# capstone_v1_1.net
KiCad netlist of a schematic drawn in Altium Designer
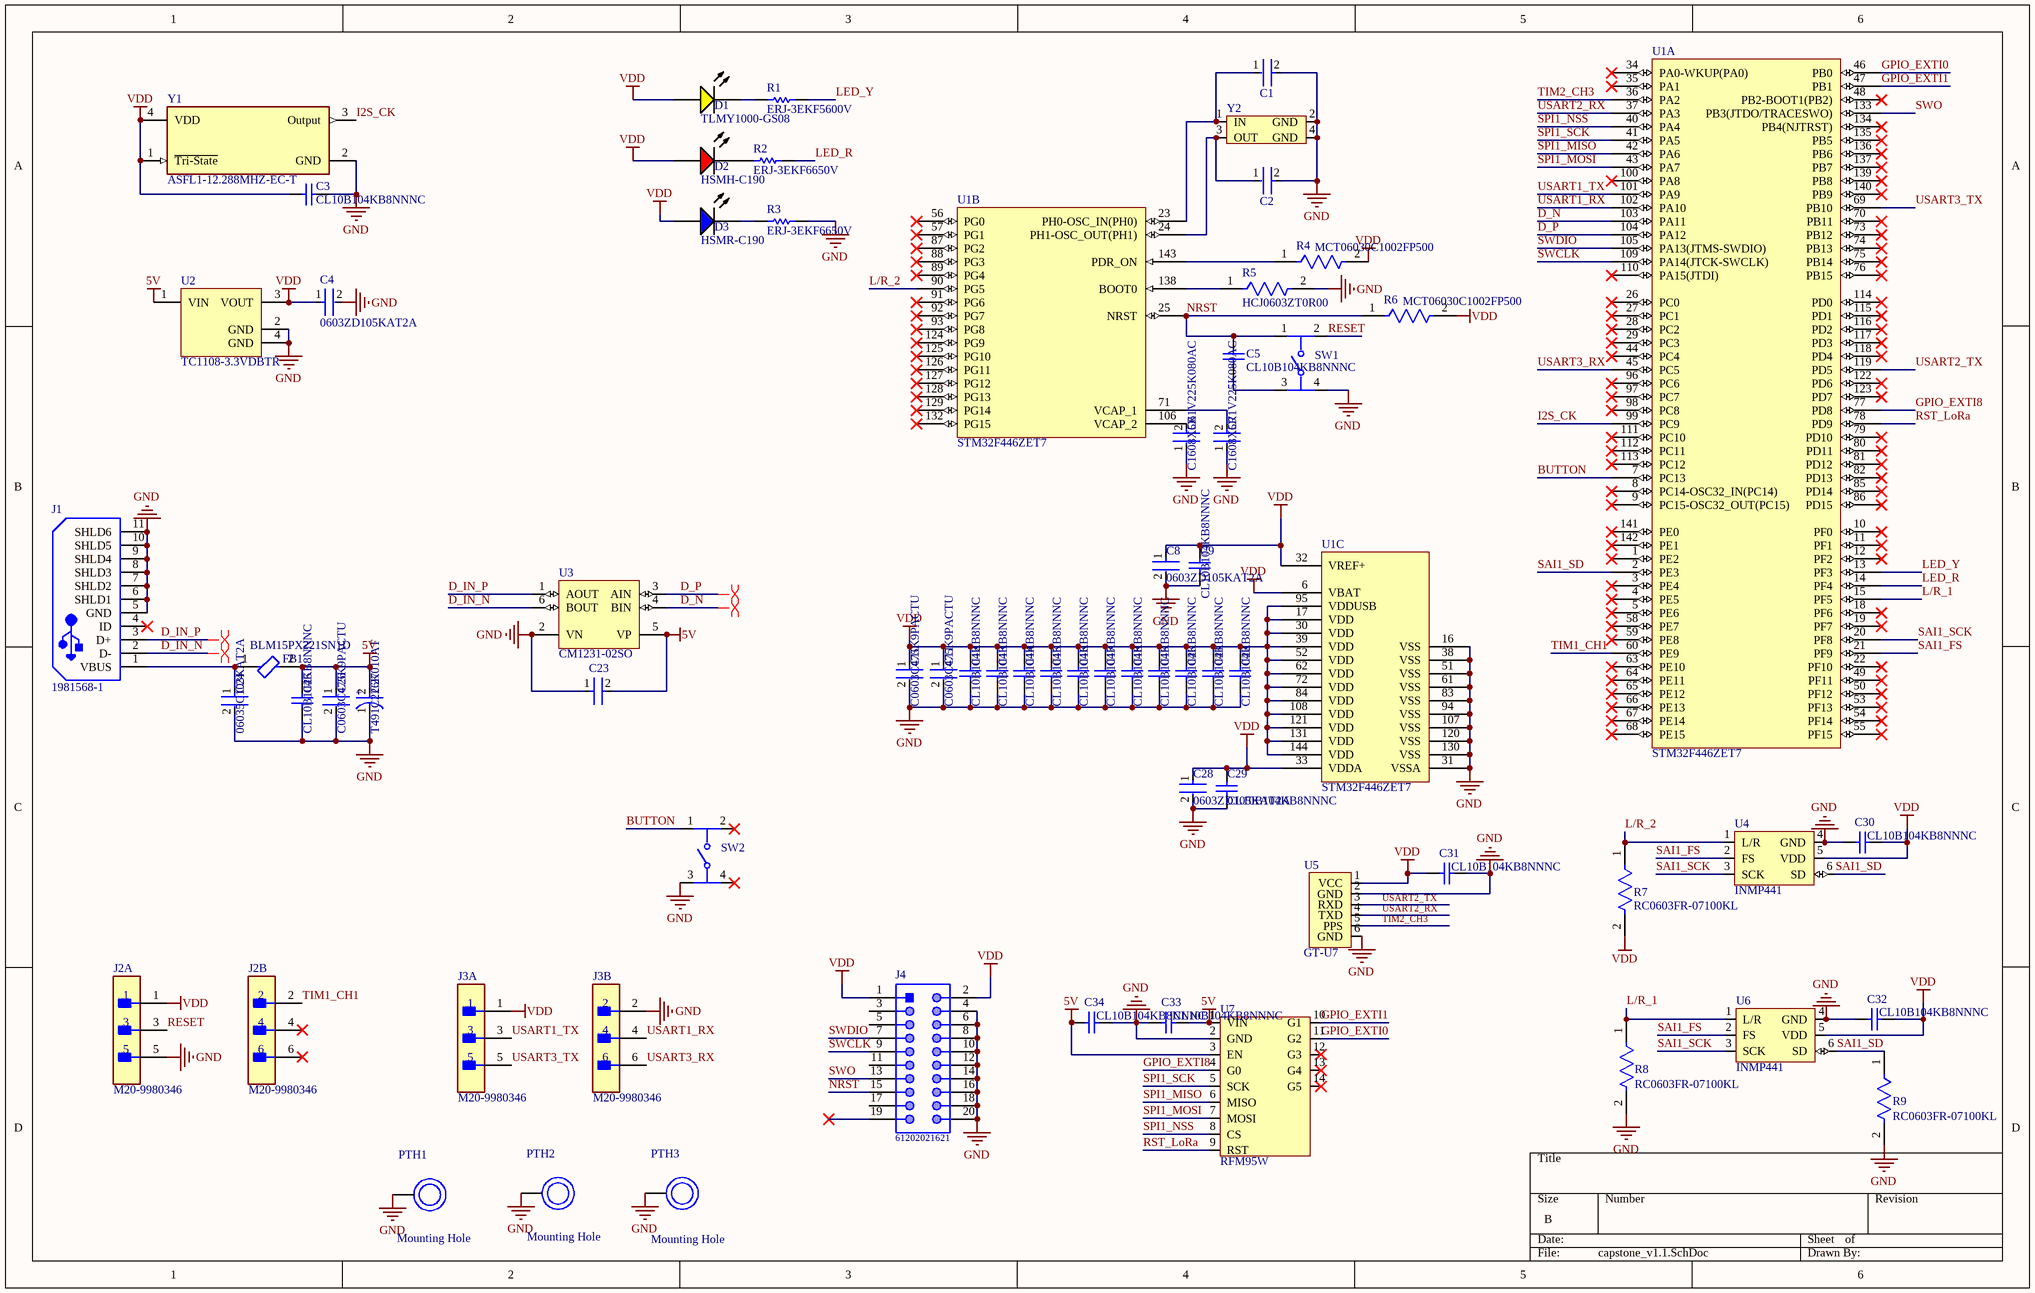
[diagram p0: capstone_v1.1.SchDoc]

(export (version "E")
  (design (tool "Eeschema 10.0.6"))
  (components
    (comp (ref "C1")
      (value "C1608C0G1H150J080AA")
      (footprint "FP-C1608-080-0_1-MFG")
      (description "Multilayer Ceramic Capacitors 15pF ±5% 50V C0G SMD 0603")
      (fields (field (name "VOLTAGE") "50V") (field (name "TOLERANCE") "5%"))
      (libsource (lib "Altium Content Vault") (part "236180d848d6139a670b325ea6854c9"))
    )
    (comp (ref "C2")
      (value "C1608C0G1H150J080AA")
      (footprint "FP-C1608-080-0_1-MFG")
      (description "Multilayer Ceramic Capacitors 15pF ±5% 50V C0G SMD 0603")
      (fields (field (name "VOLTAGE") "50V") (field (name "TOLERANCE") "5%"))
      (libsource (lib "Altium Content Vault") (part "236180d848d6139a670b325ea6854c9"))
    )
    (comp (ref "C3")
      (value "CL10B104KB8NNNC")
      (footprint "SAMS-C0603-2_M")
      (description "Multi-layer Ceramic Capacitor, -55 to 125 degC, 2-Pin SMD (0603), RoHS, Tape and Reel")
      (fields (field (name "MANUFACTURER") "Samsung Electro-Mechanics"))
      (libsource (lib "Altium Content Vault") (part "CAP-NP-2"))
    )
    (comp (ref "C4")
      (value "0603ZD105KAT2A")
      (footprint "FP-0603-L_1_6_0_15-W_0_81-IPC_A")
      (description "General Purpose Ceramic Capacitor, 0603, 1uF, 10%, X5R, 15%, 10V")
      (fields (field (name "TOLERANCE") "10%") (field (name "VOLTAGE") "10V"))
      (libsource (lib "Altium Content Vault") (part "02cd4be3c70576c341d710602a673aa"))
    )
    (comp (ref "C5")
      (value "CL10B104KB8NNNC")
      (footprint "SAMS-C0603-2_M")
      (description "Multi-layer Ceramic Capacitor, -55 to 125 degC, 2-Pin SMD (0603), RoHS, Tape and Reel")
      (fields (field (name "MANUFACTURER") "Samsung Electro-Mechanics"))
      (libsource (lib "Altium Content Vault") (part "CAP-NP-2"))
    )
    (comp (ref "C6")
      (value "C1608X5R1V225K080AC")
      (footprint "FP-C1608-080-0_1-MFG")
      (description "Multilayer Ceramic Capacitors 2.2μF ±10% 35V X5R SMD 0603")
      (fields (field (name "TOLERANCE") "10%") (field (name "VOLTAGE") "35V"))
      (libsource (lib "Altium Content Vault") (part "236180d848d6139a670b325ea6854c9"))
    )
    (comp (ref "C7")
      (value "C1608X5R1V225K080AC")
      (footprint "FP-C1608-080-0_1-MFG")
      (description "Multilayer Ceramic Capacitors 2.2μF ±10% 35V X5R SMD 0603")
      (fields (field (name "TOLERANCE") "10%") (field (name "VOLTAGE") "35V"))
      (libsource (lib "Altium Content Vault") (part "236180d848d6139a670b325ea6854c9"))
    )
    (comp (ref "C8")
      (value "0603ZD105KAT2A")
      (footprint "FP-0603-L_1_6_0_15-W_0_81-IPC_A")
      (description "General Purpose Ceramic Capacitor, 0603, 1uF, 10%, X5R, 15%, 10V")
      (fields (field (name "TOLERANCE") "10%") (field (name "VOLTAGE") "10V"))
      (libsource (lib "Altium Content Vault") (part "02cd4be3c70576c341d710602a673aa"))
    )
    (comp (ref "C9")
      (value "CL10B104KB8NNNC")
      (footprint "SAMS-C0603-2_M")
      (description "Multi-layer Ceramic Capacitor, -55 to 125 degC, 2-Pin SMD (0603), RoHS, Tape and Reel")
      (fields (field (name "MANUFACTURER") "Samsung Electro-Mechanics"))
      (libsource (lib "Altium Content Vault") (part "CAP-NP-2"))
    )
    (comp (ref "C10")
      (value "C0603C475K9PACTU")
      (footprint "FP-C0603-CG-MFG")
      (description "CAP CER 4.7UF 6.3V X5R 0603")
      (fields (field (name "TOLERANCE") "10%") (field (name "MANUFACTURER") "Kemet"))
      (libsource (lib "Altium Content Vault") (part "11868f565c42a9108669ba33697ecf6"))
    )
    (comp (ref "C11")
      (value "C0603C475K9PACTU")
      (footprint "FP-C0603-CG-MFG")
      (description "CAP CER 4.7UF 6.3V X5R 0603")
      (fields (field (name "TOLERANCE") "10%") (field (name "MANUFACTURER") "Kemet"))
      (libsource (lib "Altium Content Vault") (part "11868f565c42a9108669ba33697ecf6"))
    )
    (comp (ref "C12")
      (value "CL10B104KB8NNNC")
      (footprint "SAMS-C0603-2_M")
      (description "Multi-layer Ceramic Capacitor, -55 to 125 degC, 2-Pin SMD (0603), RoHS, Tape and Reel")
      (fields (field (name "MANUFACTURER") "Samsung Electro-Mechanics"))
      (libsource (lib "Altium Content Vault") (part "CAP-NP-2"))
    )
    (comp (ref "C13")
      (value "CL10B104KB8NNNC")
      (footprint "SAMS-C0603-2_M")
      (description "Multi-layer Ceramic Capacitor, -55 to 125 degC, 2-Pin SMD (0603), RoHS, Tape and Reel")
      (fields (field (name "MANUFACTURER") "Samsung Electro-Mechanics"))
      (libsource (lib "Altium Content Vault") (part "CAP-NP-2"))
    )
    (comp (ref "C14")
      (value "CL10B104KB8NNNC")
      (footprint "SAMS-C0603-2_M")
      (description "Multi-layer Ceramic Capacitor, -55 to 125 degC, 2-Pin SMD (0603), RoHS, Tape and Reel")
      (fields (field (name "MANUFACTURER") "Samsung Electro-Mechanics"))
      (libsource (lib "Altium Content Vault") (part "CAP-NP-2"))
    )
    (comp (ref "C15")
      (value "CL10B104KB8NNNC")
      (footprint "SAMS-C0603-2_M")
      (description "Multi-layer Ceramic Capacitor, -55 to 125 degC, 2-Pin SMD (0603), RoHS, Tape and Reel")
      (fields (field (name "MANUFACTURER") "Samsung Electro-Mechanics"))
      (libsource (lib "Altium Content Vault") (part "CAP-NP-2"))
    )
    (comp (ref "C16")
      (value "CL10B104KB8NNNC")
      (footprint "SAMS-C0603-2_M")
      (description "Multi-layer Ceramic Capacitor, -55 to 125 degC, 2-Pin SMD (0603), RoHS, Tape and Reel")
      (fields (field (name "MANUFACTURER") "Samsung Electro-Mechanics"))
      (libsource (lib "Altium Content Vault") (part "CAP-NP-2"))
    )
    (comp (ref "C17")
      (value "CL10B104KB8NNNC")
      (footprint "SAMS-C0603-2_M")
      (description "Multi-layer Ceramic Capacitor, -55 to 125 degC, 2-Pin SMD (0603), RoHS, Tape and Reel")
      (fields (field (name "MANUFACTURER") "Samsung Electro-Mechanics"))
      (libsource (lib "Altium Content Vault") (part "CAP-NP-2"))
    )
    (comp (ref "C18")
      (value "CL10B104KB8NNNC")
      (footprint "SAMS-C0603-2_M")
      (description "Multi-layer Ceramic Capacitor, -55 to 125 degC, 2-Pin SMD (0603), RoHS, Tape and Reel")
      (fields (field (name "MANUFACTURER") "Samsung Electro-Mechanics"))
      (libsource (lib "Altium Content Vault") (part "CAP-NP-2"))
    )
    (comp (ref "C19")
      (value "CL10B104KB8NNNC")
      (footprint "SAMS-C0603-2_M")
      (description "Multi-layer Ceramic Capacitor, -55 to 125 degC, 2-Pin SMD (0603), RoHS, Tape and Reel")
      (fields (field (name "MANUFACTURER") "Samsung Electro-Mechanics"))
      (libsource (lib "Altium Content Vault") (part "CAP-NP-2"))
    )
    (comp (ref "C20")
      (value "CL10B104KB8NNNC")
      (footprint "SAMS-C0603-2_M")
      (description "Multi-layer Ceramic Capacitor, -55 to 125 degC, 2-Pin SMD (0603), RoHS, Tape and Reel")
      (fields (field (name "MANUFACTURER") "Samsung Electro-Mechanics"))
      (libsource (lib "Altium Content Vault") (part "CAP-NP-2"))
    )
    (comp (ref "C21")
      (value "CL10B104KB8NNNC")
      (footprint "SAMS-C0603-2_M")
      (description "Multi-layer Ceramic Capacitor, -55 to 125 degC, 2-Pin SMD (0603), RoHS, Tape and Reel")
      (fields (field (name "MANUFACTURER") "Samsung Electro-Mechanics"))
      (libsource (lib "Altium Content Vault") (part "CAP-NP-2"))
    )
    (comp (ref "C22")
      (value "CL10B104KB8NNNC")
      (footprint "SAMS-C0603-2_M")
      (description "Multi-layer Ceramic Capacitor, -55 to 125 degC, 2-Pin SMD (0603), RoHS, Tape and Reel")
      (fields (field (name "MANUFACTURER") "Samsung Electro-Mechanics"))
      (libsource (lib "Altium Content Vault") (part "CAP-NP-2"))
    )
    (comp (ref "C23")
      (value "GRM188R71E224KA88D")
      (footprint "FP-GRM188-0_1-e0_2_0_5-IPC_C")
      (description "Chip Multilayer Ceramic Capacitors for General Purpose, 0603, 0.22uF, X7R, 15%, 10%, 25V")
      (fields (field (name "TOLERANCE") "10%") (field (name "VOLTAGE") "50V"))
      (libsource (lib "Altium Content Vault") (part "11868f565c42a9108669ba33697ecf6"))
    )
    (comp (ref "C24")
      (value "06035C103KAT2A")
      (footprint "FP-0603-L_1_6_0_15-W_0_81-MFG")
      (description "General Purpose Ceramic Capacitor, 0603, 10nF, 10%, X7R, 15%, 50V")
      (fields (field (name "VOLTAGE") "50V") (field (name "TOLERANCE") "10%"))
      (libsource (lib "Altium Content Vault") (part "02cd4be3c70576c341d710602a673aa"))
    )
    (comp (ref "C25")
      (value "CL10B104KB8NNNC")
      (footprint "SAMS-C0603-2_M")
      (description "Multi-layer Ceramic Capacitor, -55 to 125 degC, 2-Pin SMD (0603), RoHS, Tape and Reel")
      (fields (field (name "MANUFACTURER") "Samsung Electro-Mechanics"))
      (libsource (lib "Altium Content Vault") (part "CAP-NP-2"))
    )
    (comp (ref "C26")
      (value "C0603C475K9PACTU")
      (footprint "FP-C0603-CG-MFG")
      (description "CAP CER 4.7UF 6.3V X5R 0603")
      (fields (field (name "TOLERANCE") "10%") (field (name "MANUFACTURER") "Kemet"))
      (libsource (lib "Altium Content Vault") (part "11868f565c42a9108669ba33697ecf6"))
    )
    (comp (ref "C27")
      (value "T491C226K010AT")
      (footprint "FP-T491C226K010AT-MFG")
      (description "CAP TANT 22UF 10% 10V 2312")
      (fields (field (name "TOLERANCE") "20%") (field (name "VOLTAGE") "10V"))
      (libsource (lib "Altium Content Vault") (part "a00bbbee19879c290e62620ae7e47b1"))
    )
    (comp (ref "C28")
      (value "0603ZD105KAT2A")
      (footprint "FP-0603-L_1_6_0_15-W_0_81-IPC_A")
      (description "General Purpose Ceramic Capacitor, 0603, 1uF, 10%, X5R, 15%, 10V")
      (fields (field (name "TOLERANCE") "10%") (field (name "VOLTAGE") "10V"))
      (libsource (lib "Altium Content Vault") (part "02cd4be3c70576c341d710602a673aa"))
    )
    (comp (ref "C29")
      (value "CL10B104KB8NNNC")
      (footprint "SAMS-C0603-2_M")
      (description "Multi-layer Ceramic Capacitor, -55 to 125 degC, 2-Pin SMD (0603), RoHS, Tape and Reel")
      (fields (field (name "MANUFACTURER") "Samsung Electro-Mechanics"))
      (libsource (lib "Altium Content Vault") (part "CAP-NP-2"))
    )
    (comp (ref "C30")
      (value "CL10B104KB8NNNC")
      (footprint "SAMS-C0603-2_M")
      (description "Multi-layer Ceramic Capacitor, -55 to 125 degC, 2-Pin SMD (0603), RoHS, Tape and Reel")
      (fields (field (name "MANUFACTURER") "Samsung Electro-Mechanics"))
      (libsource (lib "Altium Content Vault") (part "CAP-NP-2"))
    )
    (comp (ref "C31")
      (value "CL10B104KB8NNNC")
      (footprint "SAMS-C0603-2_M")
      (description "Multi-layer Ceramic Capacitor, -55 to 125 degC, 2-Pin SMD (0603), RoHS, Tape and Reel")
      (fields (field (name "MANUFACTURER") "Samsung Electro-Mechanics"))
      (libsource (lib "Altium Content Vault") (part "CAP-NP-2"))
    )
    (comp (ref "C32")
      (value "CL10B104KB8NNNC")
      (footprint "SAMS-C0603-2_M")
      (description "Multi-layer Ceramic Capacitor, -55 to 125 degC, 2-Pin SMD (0603), RoHS, Tape and Reel")
      (fields (field (name "MANUFACTURER") "Samsung Electro-Mechanics"))
      (libsource (lib "Altium Content Vault") (part "CAP-NP-2"))
    )
    (comp (ref "C33")
      (value "CL10B104KB8NNNC")
      (footprint "SAMS-C0603-2_M")
      (description "Multi-layer Ceramic Capacitor, -55 to 125 degC, 2-Pin SMD (0603), RoHS, Tape and Reel")
      (fields (field (name "MANUFACTURER") "Samsung Electro-Mechanics"))
      (libsource (lib "Altium Content Vault") (part "CAP-NP-2"))
    )
    (comp (ref "C34")
      (value "CL10B104KB8NNNC")
      (footprint "SAMS-C0603-2_M")
      (description "Multi-layer Ceramic Capacitor, -55 to 125 degC, 2-Pin SMD (0603), RoHS, Tape and Reel")
      (fields (field (name "MANUFACTURER") "Samsung Electro-Mechanics"))
      (libsource (lib "Altium Content Vault") (part "CAP-NP-2"))
    )
    (comp (ref "D1")
      (value "TLMY1000-GS08")
      (footprint "VISH-TLMY1000_V")
      (description "Low Current LED, 40 mW, -40 to 100 degC, 2-Pin SMD, RoHS, Tape and Reel")
      (fields (field (name "MANUFACTURER") "Vishay"))
      (libsource (lib "Altium Content Vault") (part "LED-YELLOW-AK-2"))
    )
    (comp (ref "D2")
      (value "HSMH-C190")
      (footprint "AVAG-HSMX-C190_V")
      (description "LED Uni-Color Red, 65 mW, 20 mA, -40 to 85 degC, 2-Pin SMD, RoHS, Tape and Reel")
      (libsource (lib "Altium Content Vault") (part "LED-RED-AK-2"))
    )
    (comp (ref "D3")
      (value "HSMR-C190")
      (footprint "AVAG-HSMX-C190_V")
      (description "LED Uni-Color Blue, 78 mW, 20 mA, -40 to 85 degC, 2-Pin SMD, RoHS, Tape and Reel")
      (libsource (lib "Altium Content Vault") (part "LED-BLUE-AK-2"))
    )
    (comp (ref "FB1")
      (value "BLM15PX221SN1D")
      (footprint "FP-BLM15-0_05-IPC_A")
      (description "Chip Ferrite Bead, 0402, 220Ω @ 100MHz, 0.1Ω, 25%, 1.4A")
      (fields (field (name "TOLERANCE") "25%"))
      (libsource (lib "Altium Content Vault") (part "5f30dd21d616792df468990f7003faa"))
    )
    (comp (ref "J1")
      (value "1981568-1")
      (footprint "TECO-1981568-5_V")
      (description "Micro USB Receptacle Standard Type B Assy, 5-Pin SMD, RoHS, Tape and Reel")
      (fields (field (name "MANUFACTURER") "TE Connectivity"))
      (libsource (lib "Altium Content Vault") (part "USB-5-6SHLD"))
    )
    (comp (ref "J2")
      (value "M20-9980346")
      (footprint "FP-M20-9980346-MFG")
      (description "CONN HEADER VERT 6POS 2.54MM")
      (fields
        (field (name "MANUFACTURER") "Harwin")
        (field (name "OCTOPART") "https://octopart.com/m20-9980346-harwin-5436545")
      )
      (libsource (lib "Altium Content Vault") (part "2654a11fb13586ecb194516b1c997bc"))
    )
    (comp (ref "J3")
      (value "M20-9980346")
      (footprint "FP-M20-9980346-MFG")
      (description "CONN HEADER VERT 6POS 2.54MM")
      (fields
        (field (name "MANUFACTURER") "Harwin")
        (field (name "OCTOPART") "https://octopart.com/m20-9980346-harwin-5436545")
      )
      (libsource (lib "Altium Content Vault") (part "2654a11fb13586ecb194516b1c997bc"))
    )
    (comp (ref "J4")
      (value "61202021621")
      (footprint "61202021621")
      (description "Male Box Header WR-BHD, THT, Vertical, pitch 2.54 mm, 20 pins")
      (fields (field (name "MANUFACTURER") "Wurth Elektronik") (field (name "PUBLISHER") "WurthElektronik"))
      (libsource (lib "Altium Content Vault") (part "WE-CN-2P-M-R20"))
    )
    (comp (ref "PTH1")
      (value "Mounting Hole")
      (footprint "MB Stand off")
      (description "MB Standoffs")
      (libsource (lib "capstone_v1.1") (part "Mounting Hole"))
    )
    (comp (ref "PTH2")
      (value "Mounting Hole")
      (footprint "MB Stand off")
      (description "MB Standoffs")
      (libsource (lib "capstone_v1.1") (part "Mounting Hole"))
    )
    (comp (ref "PTH3")
      (value "Mounting Hole")
      (footprint "MB Stand off")
      (description "MB Standoffs")
      (libsource (lib "capstone_v1.1") (part "Mounting Hole"))
    )
    (comp (ref "R1")
      (value "ERJ-3EKF5600V")
      (footprint "RESC1608X55X30ML15T15")
      (description "Chip Resistor, 560 Ohm, +/- 1%, 0.1 W, -55 to 155 degC, 0603 (1608 Metric), RoHS, Tape and Reel")
      (libsource (lib "Altium Content Vault") (part "RES-2"))
    )
    (comp (ref "R2")
      (value "ERJ-3EKF6650V")
      (footprint "RESC1608X55X30ML15T15")
      (fields (field (name "MANUFACTURER") "Panasonic"))
      (libsource (lib "Altium Content Vault") (part "RES"))
    )
    (comp (ref "R3")
      (value "ERJ-3EKF6650V")
      (footprint "RESC1608X55X30ML15T15")
      (fields (field (name "MANUFACTURER") "Panasonic"))
      (libsource (lib "Altium Content Vault") (part "RES"))
    )
    (comp (ref "R4")
      (value "MCT06030C1002FP500")
      (footprint "FP-MCT0603-IPC_C")
      (description "RES SMD 100 OHM 1% 1/8W 0603")
      (fields (field (name "TOLERANCE") "1%"))
      (libsource (lib "Altium Content Vault") (part "1029c3af85768c4190bb7ad29bc67b5"))
    )
    (comp (ref "R5")
      (value "HCJ0603ZT0R00")
      (footprint "FP-HCJ0603-MFG")
      (description "RES 0 OHM JUMPER 1/4W 0603")
      (libsource (lib "Altium Content Vault") (part "1029c3af85768c4190bb7ad29bc67b5"))
    )
    (comp (ref "R6")
      (value "MCT06030C1002FP500")
      (footprint "FP-MCT0603-IPC_C")
      (description "RES SMD 100 OHM 1% 1/8W 0603")
      (fields (field (name "TOLERANCE") "1%"))
      (libsource (lib "Altium Content Vault") (part "1029c3af85768c4190bb7ad29bc67b5"))
    )
    (comp (ref "R7")
      (value "RC0603FR-07100KL")
      (footprint "FP-RC0603-0_55-MFG")
      (description "RES SMD 100K OHM 1% 1/10W 0603")
      (fields (field (name "TOLERANCE") "1%"))
      (libsource (lib "Altium Content Vault") (part "1029c3af85768c4190bb7ad29bc67b5"))
    )
    (comp (ref "R8")
      (value "RC0603FR-07100KL")
      (footprint "FP-RC0603-0_55-MFG")
      (description "RES SMD 100K OHM 1% 1/10W 0603")
      (fields (field (name "TOLERANCE") "1%"))
      (libsource (lib "Altium Content Vault") (part "1029c3af85768c4190bb7ad29bc67b5"))
    )
    (comp (ref "R9")
      (value "RC0603FR-07100KL")
      (footprint "FP-RC0603-0_55-MFG")
      (description "RES SMD 100K OHM 1% 1/10W 0603")
      (fields (field (name "TOLERANCE") "1%"))
      (libsource (lib "Altium Content Vault") (part "1029c3af85768c4190bb7ad29bc67b5"))
    )
    (comp (ref "SW1")
      (value "PTS645SM43SMTR92LFS")
      (footprint "FP-PTS645SM43SMTR92LFS-MFG")
      (description "SWITCH TACTILE SPST-NO 0.05A 12V")
      (libsource (lib "Altium Content Vault") (part "1adf0dd01260c80cf25a44bfd6b99ba"))
    )
    (comp (ref "SW2")
      (value "PTS645SM43SMTR92LFS")
      (footprint "FP-PTS645SM43SMTR92LFS-MFG")
      (description "SWITCH TACTILE SPST-NO 0.05A 12V")
      (libsource (lib "Altium Content Vault") (part "1adf0dd01260c80cf25a44bfd6b99ba"))
    )
    (comp (ref "U1")
      (value "STM32F446ZET7")
      (footprint "STM-LQFP144_M")
      (libsource (lib "Altium Content Vault") (part "MC-ARM-STM32F446-LQFP144"))
    )
    (comp (ref "U2")
      (value "TC1108-3.3VDBTR")
      (footprint "SOT-223-DB3_L")
      (description "300mA CMOS LDO, 3-Pin SOT-223, Extended Temperature, Tape and Reel")
      (libsource (lib "Altium Content Vault") (part "PM-LINEREG-TC1108-IL4"))
    )
    (comp (ref "U3")
      (value "CM1231-02SO")
      (footprint "ONSC-SOT23-6-527AJ_V")
      (description "2-Channel Low-Capacitance ESD Protection Array, 6-Pin SOT-23, Pb-Free, Tape and Reel")
      (fields (field (name "MANUFACTURER") "On Semiconductor"))
      (libsource (lib "Altium Content Vault") (part "ONSC-CM1231-02SO-SOT-23-6-527AJ"))
    )
    (comp (ref "U4")
      (value "INMP441")
      (footprint "INMP441")
      (description "Microphone Module")
      (libsource (lib "capstone_v1.1") (part "INM4P441"))
    )
    (comp (ref "U5")
      (value "GT-U7")
      (footprint "GT U7 GPS")
      (description "GPS Module")
      (libsource (lib "capstone_v1.1") (part "GT-U7"))
    )
    (comp (ref "U6")
      (value "INMP441")
      (footprint "INMP441")
      (description "Microphone Module")
      (libsource (lib "capstone_v1.1") (part "INM4P441"))
    )
    (comp (ref "U7")
      (value "RFM95W")
      (footprint "RFM95W")
      (description "LoRa Module")
      (libsource (lib "capstone_v1.1") (part "RFM95W"))
    )
    (comp (ref "Y1")
      (value "ASFL1-12.288MHZ-EC-T")
      (footprint "FP-ASFL1-MFG")
      (description "XTAL Oscillator 12.288MHz ±50ppm HCMOS, TTL 3.3V 4-SMD 5mm x 3.2mm")
      (libsource (lib "Altium Content Vault") (part "47df00dc2349451232cb22fac08fbff"))
    )
    (comp (ref "Y2")
      (value "2151-RH100-8.000-10-1010-EXT-TRCT-ND")
      (footprint "2151-RH100-8.000-10-1010-EXT-TRCT-ND")
      (description "8 MHz Oscillator")
      (libsource (lib "capstone_v1.1") (part "2151-RH100-8.000-10-1010-EXT-TRCT-ND"))
    )
  )
  (nets
    (net (code "1") (name "/BUTTON") (class "Default")
      (node (ref "SW2") (pin "1") (pinfunction "1_1") (pintype "passive"))
      (node (ref "U1") (pin "7") (pinfunction "PC13_7") (pintype "bidirectional"))
    )
    (net (code "2") (name "/D_IN_N") (class "Default")
      (node (ref "J1") (pin "2") (pinfunction "D-_2") (pintype "passive"))
      (node (ref "U3") (pin "6") (pinfunction "BOUT_6") (pintype "bidirectional"))
    )
    (net (code "3") (name "/D_IN_P") (class "Default")
      (node (ref "J1") (pin "3") (pinfunction "D+_3") (pintype "passive"))
      (node (ref "U3") (pin "1") (pinfunction "AOUT_1") (pintype "bidirectional"))
    )
    (net (code "4") (name "/D_N") (class "Default")
      (node (ref "U1") (pin "103") (pinfunction "PA11_103") (pintype "bidirectional"))
      (node (ref "U3") (pin "4") (pinfunction "BIN_4") (pintype "bidirectional"))
    )
    (net (code "5") (name "/D_P") (class "Default")
      (node (ref "U1") (pin "104") (pinfunction "PA12_104") (pintype "bidirectional"))
      (node (ref "U3") (pin "3") (pinfunction "AIN_3") (pintype "bidirectional"))
    )
    (net (code "6") (name "/GPIO_EXTI0") (class "Default")
      (node (ref "U1") (pin "46") (pinfunction "PB0_46") (pintype "bidirectional"))
      (node (ref "U7") (pin "11") (pinfunction "G2_11") (pintype "passive"))
    )
    (net (code "7") (name "/GPIO_EXTI1") (class "Default")
      (node (ref "U1") (pin "47") (pinfunction "PB1_47") (pintype "bidirectional"))
      (node (ref "U7") (pin "10") (pinfunction "G1_10") (pintype "passive"))
    )
    (net (code "8") (name "/GPIO_EXTI8") (class "Default")
      (node (ref "U1") (pin "77") (pinfunction "PD8_77") (pintype "bidirectional"))
      (node (ref "U7") (pin "4") (pinfunction "G0_4") (pintype "passive"))
    )
    (net (code "9") (name "/I2S_CK") (class "Default")
      (node (ref "U1") (pin "99") (pinfunction "PC9_99") (pintype "bidirectional"))
      (node (ref "Y1") (pin "3") (pinfunction "Output_3") (pintype "output"))
    )
    (net (code "10") (name "/LED_R") (class "Default")
      (node (ref "R2") (pin "2") (pinfunction "2_2") (pintype "passive"))
      (node (ref "U1") (pin "14") (pinfunction "PF4_14") (pintype "bidirectional"))
    )
    (net (code "11") (name "/LED_Y") (class "Default")
      (node (ref "R1") (pin "2") (pinfunction "2_2") (pintype "passive"))
      (node (ref "U1") (pin "13") (pinfunction "PF3_13") (pintype "bidirectional"))
    )
    (net (code "12") (name "/L{slash}R_1") (class "Default")
      (node (ref "R8") (pin "1") (pinfunction "1_1") (pintype "passive"))
      (node (ref "U1") (pin "15") (pinfunction "PF5_15") (pintype "bidirectional"))
      (node (ref "U6") (pin "1") (pinfunction "L/R_1") (pintype "input"))
    )
    (net (code "13") (name "/L{slash}R_2") (class "Default")
      (node (ref "R7") (pin "1") (pinfunction "1_1") (pintype "passive"))
      (node (ref "U1") (pin "90") (pinfunction "PG5_90") (pintype "bidirectional"))
      (node (ref "U4") (pin "1") (pinfunction "L/R_1") (pintype "input"))
    )
    (net (code "14") (name "/NRST") (class "Default")
      (node (ref "C5") (pin "2") (pinfunction "2_2") (pintype "passive"))
      (node (ref "J4") (pin "15") (pinfunction "15_15") (pintype "passive"))
      (node (ref "R6") (pin "1") (pinfunction "1_1") (pintype "passive"))
      (node (ref "SW1") (pin "1") (pinfunction "1_1") (pintype "passive"))
      (node (ref "U1") (pin "25") (pinfunction "NRST_25") (pintype "bidirectional"))
    )
    (net (code "15") (name "/RESET") (class "Default")
      (node (ref "J2") (pin "3") (pinfunction "3_3") (pintype "passive"))
      (node (ref "SW1") (pin "2") (pinfunction "2_2") (pintype "passive"))
    )
    (net (code "16") (name "/RST_LoRa") (class "Default")
      (node (ref "U1") (pin "78") (pinfunction "PD9_78") (pintype "bidirectional"))
      (node (ref "U7") (pin "9") (pinfunction "RST_9") (pintype "input"))
    )
    (net (code "17") (name "/SAI1_FS") (class "Default")
      (node (ref "U1") (pin "21") (pinfunction "PF9_21") (pintype "bidirectional"))
      (node (ref "U4") (pin "2") (pinfunction "FS_2") (pintype "input"))
      (node (ref "U6") (pin "2") (pinfunction "FS_2") (pintype "input"))
    )
    (net (code "18") (name "/SAI1_SCK") (class "Default")
      (node (ref "U1") (pin "20") (pinfunction "PF8_20") (pintype "bidirectional"))
      (node (ref "U4") (pin "3") (pinfunction "SCK_3") (pintype "input"))
      (node (ref "U6") (pin "3") (pinfunction "SCK_3") (pintype "input"))
    )
    (net (code "19") (name "/SAI1_SD") (class "Default")
      (node (ref "R9") (pin "1") (pinfunction "1_1") (pintype "passive"))
      (node (ref "U1") (pin "2") (pinfunction "PE3_2") (pintype "bidirectional"))
      (node (ref "U4") (pin "6") (pinfunction "SD_6") (pintype "bidirectional"))
      (node (ref "U6") (pin "6") (pinfunction "SD_6") (pintype "bidirectional"))
    )
    (net (code "20") (name "/SPI1_MISO") (class "Default")
      (node (ref "U1") (pin "42") (pinfunction "PA6_42") (pintype "bidirectional"))
      (node (ref "U7") (pin "6") (pinfunction "MISO_6") (pintype "output"))
    )
    (net (code "21") (name "/SPI1_MOSI") (class "Default")
      (node (ref "U1") (pin "43") (pinfunction "PA7_43") (pintype "bidirectional"))
      (node (ref "U7") (pin "7") (pinfunction "MOSI_7") (pintype "input"))
    )
    (net (code "22") (name "/SPI1_NSS") (class "Default")
      (node (ref "U1") (pin "40") (pinfunction "PA4_40") (pintype "bidirectional"))
      (node (ref "U7") (pin "8") (pinfunction "CS_8") (pintype "input"))
    )
    (net (code "23") (name "/SPI1_SCK") (class "Default")
      (node (ref "U1") (pin "41") (pinfunction "PA5_41") (pintype "bidirectional"))
      (node (ref "U7") (pin "5") (pinfunction "SCK_5") (pintype "input"))
    )
    (net (code "24") (name "/SWCLK") (class "Default")
      (node (ref "J4") (pin "9") (pinfunction "9_9") (pintype "passive"))
      (node (ref "U1") (pin "109") (pinfunction "PA14(JTCK-SWCLK)_109") (pintype "bidirectional"))
    )
    (net (code "25") (name "/SWDIO") (class "Default")
      (node (ref "J4") (pin "7") (pinfunction "7_7") (pintype "passive"))
      (node (ref "U1") (pin "105") (pinfunction "PA13(JTMS-SWDIO)_105") (pintype "bidirectional"))
    )
    (net (code "26") (name "/SWO") (class "Default")
      (node (ref "J4") (pin "13") (pinfunction "13_13") (pintype "passive"))
      (node (ref "U1") (pin "133") (pinfunction "PB3(JTDO/TRACESWO)_133") (pintype "bidirectional"))
    )
    (net (code "27") (name "/TIM1_CH1") (class "Default")
      (node (ref "J2") (pin "2") (pinfunction "2_2") (pintype "passive"))
      (node (ref "U1") (pin "60") (pinfunction "PE9_60") (pintype "bidirectional"))
    )
    (net (code "28") (name "/TIM2_CH3") (class "Default")
      (node (ref "U1") (pin "36") (pinfunction "PA2_36") (pintype "bidirectional"))
      (node (ref "U5") (pin "5") (pinfunction "PPS_5") (pintype "output"))
    )
    (net (code "29") (name "/USART1_RX") (class "Default")
      (node (ref "J3") (pin "4") (pinfunction "4_4") (pintype "passive"))
      (node (ref "U1") (pin "102") (pinfunction "PA10_102") (pintype "bidirectional"))
    )
    (net (code "30") (name "/USART1_TX") (class "Default")
      (node (ref "J3") (pin "3") (pinfunction "3_3") (pintype "passive"))
      (node (ref "U1") (pin "101") (pinfunction "PA9_101") (pintype "bidirectional"))
    )
    (net (code "31") (name "/USART2_RX") (class "Default")
      (node (ref "U1") (pin "37") (pinfunction "PA3_37") (pintype "bidirectional"))
      (node (ref "U5") (pin "4") (pinfunction "TXD_4") (pintype "output"))
    )
    (net (code "32") (name "/USART2_TX") (class "Default")
      (node (ref "U1") (pin "119") (pinfunction "PD5_119") (pintype "bidirectional"))
      (node (ref "U5") (pin "3") (pinfunction "RXD_3") (pintype "input"))
    )
    (net (code "33") (name "/USART3_RX") (class "Default")
      (node (ref "J3") (pin "6") (pinfunction "6_6") (pintype "passive"))
      (node (ref "U1") (pin "45") (pinfunction "PC5_45") (pintype "bidirectional"))
    )
    (net (code "34") (name "/USART3_TX") (class "Default")
      (node (ref "J3") (pin "5") (pinfunction "5_5") (pintype "passive"))
      (node (ref "U1") (pin "69") (pinfunction "PB10_69") (pintype "bidirectional"))
    )
    (net (code "35") (name "5V") (class "Default")
      (node (ref "C23") (pin "2") (pinfunction "2_2") (pintype "passive"))
      (node (ref "C25") (pin "2") (pinfunction "2_2") (pintype "passive"))
      (node (ref "C26") (pin "1") (pinfunction "1_1") (pintype "passive"))
      (node (ref "C27") (pin "2") (pinfunction "A_2") (pintype "passive"))
      (node (ref "C33") (pin "1") (pinfunction "1_1") (pintype "passive"))
      (node (ref "C34") (pin "2") (pinfunction "2_2") (pintype "passive"))
      (node (ref "FB1") (pin "2") (pinfunction "2_2") (pintype "passive"))
      (node (ref "U2") (pin "1") (pinfunction "VIN_1") (pintype "power_in"))
      (node (ref "U3") (pin "5") (pinfunction "VP_5") (pintype "power_in"))
      (node (ref "U7") (pin "1") (pinfunction "VIN_1") (pintype "power_in"))
      (node (ref "U7") (pin "3") (pinfunction "EN_3") (pintype "input"))
    )
    (net (code "36") (name "GND") (class "Default")
      (node (ref "C1") (pin "2") (pinfunction "2_2") (pintype "passive"))
      (node (ref "C10") (pin "2") (pinfunction "2_2") (pintype "passive"))
      (node (ref "C11") (pin "2") (pinfunction "2_2") (pintype "passive"))
      (node (ref "C12") (pin "1") (pinfunction "1_1") (pintype "passive"))
      (node (ref "C13") (pin "1") (pinfunction "1_1") (pintype "passive"))
      (node (ref "C14") (pin "1") (pinfunction "1_1") (pintype "passive"))
      (node (ref "C15") (pin "1") (pinfunction "1_1") (pintype "passive"))
      (node (ref "C16") (pin "1") (pinfunction "1_1") (pintype "passive"))
      (node (ref "C17") (pin "1") (pinfunction "1_1") (pintype "passive"))
      (node (ref "C18") (pin "1") (pinfunction "1_1") (pintype "passive"))
      (node (ref "C19") (pin "1") (pinfunction "1_1") (pintype "passive"))
      (node (ref "C2") (pin "2") (pinfunction "2_2") (pintype "passive"))
      (node (ref "C20") (pin "1") (pinfunction "1_1") (pintype "passive"))
      (node (ref "C21") (pin "1") (pinfunction "1_1") (pintype "passive"))
      (node (ref "C22") (pin "1") (pinfunction "1_1") (pintype "passive"))
      (node (ref "C23") (pin "1") (pinfunction "1_1") (pintype "passive"))
      (node (ref "C24") (pin "2") (pinfunction "2_2") (pintype "passive"))
      (node (ref "C25") (pin "1") (pinfunction "1_1") (pintype "passive"))
      (node (ref "C26") (pin "2") (pinfunction "2_2") (pintype "passive"))
      (node (ref "C27") (pin "1") (pinfunction "C_1") (pintype "passive"))
      (node (ref "C28") (pin "2") (pinfunction "2_2") (pintype "passive"))
      (node (ref "C29") (pin "1") (pinfunction "1_1") (pintype "passive"))
      (node (ref "C3") (pin "1") (pinfunction "1_1") (pintype "passive"))
      (node (ref "C30") (pin "2") (pinfunction "2_2") (pintype "passive"))
      (node (ref "C31") (pin "1") (pinfunction "1_1") (pintype "passive"))
      (node (ref "C32") (pin "2") (pinfunction "2_2") (pintype "passive"))
      (node (ref "C33") (pin "2") (pinfunction "2_2") (pintype "passive"))
      (node (ref "C34") (pin "1") (pinfunction "1_1") (pintype "passive"))
      (node (ref "C4") (pin "2") (pinfunction "2_2") (pintype "passive"))
      (node (ref "C6") (pin "1") (pinfunction "1_1") (pintype "passive"))
      (node (ref "C7") (pin "1") (pinfunction "1_1") (pintype "passive"))
      (node (ref "C8") (pin "2") (pinfunction "2_2") (pintype "passive"))
      (node (ref "C9") (pin "1") (pinfunction "1_1") (pintype "passive"))
      (node (ref "J1") (pin "10") (pinfunction "SHLD5_10") (pintype "passive"))
      (node (ref "J1") (pin "11") (pinfunction "SHLD6_11") (pintype "passive"))
      (node (ref "J1") (pin "5") (pinfunction "GND_5") (pintype "passive"))
      (node (ref "J1") (pin "6") (pinfunction "SHLD1_6") (pintype "passive"))
      (node (ref "J1") (pin "7") (pinfunction "SHLD2_7") (pintype "passive"))
      (node (ref "J1") (pin "8") (pinfunction "SHLD3_8") (pintype "passive"))
      (node (ref "J1") (pin "9") (pinfunction "SHLD4_9") (pintype "passive"))
      (node (ref "J2") (pin "5") (pinfunction "5_5") (pintype "passive"))
      (node (ref "J3") (pin "2") (pinfunction "2_2") (pintype "passive"))
      (node (ref "J4") (pin "10") (pinfunction "10_10") (pintype "passive"))
      (node (ref "J4") (pin "12") (pinfunction "12_12") (pintype "passive"))
      (node (ref "J4") (pin "14") (pinfunction "14_14") (pintype "passive"))
      (node (ref "J4") (pin "16") (pinfunction "16_16") (pintype "passive"))
      (node (ref "J4") (pin "18") (pinfunction "18_18") (pintype "passive"))
      (node (ref "J4") (pin "20") (pinfunction "20_20") (pintype "passive"))
      (node (ref "J4") (pin "4") (pinfunction "4_4") (pintype "passive"))
      (node (ref "J4") (pin "6") (pinfunction "6_6") (pintype "passive"))
      (node (ref "J4") (pin "8") (pinfunction "8_8") (pintype "passive"))
      (node (ref "PTH1") (pin "1") (pinfunction "1_1") (pintype "power_in"))
      (node (ref "PTH2") (pin "1") (pinfunction "1_1") (pintype "power_in"))
      (node (ref "PTH3") (pin "1") (pinfunction "1_1") (pintype "power_in"))
      (node (ref "R3") (pin "2") (pinfunction "2_2") (pintype "passive"))
      (node (ref "R5") (pin "2") (pinfunction "2_2") (pintype "passive"))
      (node (ref "R8") (pin "2") (pinfunction "2_2") (pintype "passive"))
      (node (ref "R9") (pin "2") (pinfunction "2_2") (pintype "passive"))
      (node (ref "SW1") (pin "4") (pinfunction "4_4") (pintype "passive"))
      (node (ref "SW2") (pin "3") (pinfunction "3_3") (pintype "passive"))
      (node (ref "U1") (pin "107") (pinfunction "VSS_107") (pintype "power_in"))
      (node (ref "U1") (pin "120") (pinfunction "VSS_120") (pintype "power_in"))
      (node (ref "U1") (pin "130") (pinfunction "VSS_130") (pintype "power_in"))
      (node (ref "U1") (pin "16") (pinfunction "VSS_16") (pintype "power_in"))
      (node (ref "U1") (pin "31") (pinfunction "VSSA_31") (pintype "power_in"))
      (node (ref "U1") (pin "38") (pinfunction "VSS_38") (pintype "power_in"))
      (node (ref "U1") (pin "51") (pinfunction "VSS_51") (pintype "power_in"))
      (node (ref "U1") (pin "61") (pinfunction "VSS_61") (pintype "power_in"))
      (node (ref "U1") (pin "83") (pinfunction "VSS_83") (pintype "power_in"))
      (node (ref "U1") (pin "94") (pinfunction "VSS_94") (pintype "power_in"))
      (node (ref "U2") (pin "2") (pinfunction "GND_2") (pintype "power_in"))
      (node (ref "U2") (pin "4") (pinfunction "GND_4") (pintype "power_in"))
      (node (ref "U3") (pin "2") (pinfunction "VN_2") (pintype "power_in"))
      (node (ref "U4") (pin "4") (pinfunction "GND_4") (pintype "power_in"))
      (node (ref "U5") (pin "2") (pinfunction "GND_2") (pintype "power_in"))
      (node (ref "U5") (pin "6") (pinfunction "GND_6") (pintype "power_in"))
      (node (ref "U6") (pin "4") (pinfunction "GND_4") (pintype "power_in"))
      (node (ref "U7") (pin "2") (pinfunction "GND_2") (pintype "power_in"))
      (node (ref "Y1") (pin "2") (pinfunction "GND_2") (pintype "power_in"))
      (node (ref "Y2") (pin "2") (pinfunction "GND_2") (pintype "power_in"))
      (node (ref "Y2") (pin "4") (pinfunction "GND_4") (pintype "power_in"))
    )
    (net (code "37") (name "Net-(C5-Pad1)") (class "Default")
      (node (ref "C5") (pin "1") (pinfunction "1_1") (pintype "passive"))
      (node (ref "SW1") (pin "3") (pinfunction "3_3") (pintype "passive"))
    )
    (net (code "38") (name "Net-(D1-K)") (class "Default")
      (node (ref "D1") (pin "2") (pinfunction "K_2") (pintype "passive"))
      (node (ref "R1") (pin "1") (pinfunction "1_1") (pintype "passive"))
    )
    (net (code "39") (name "Net-(D2-K)") (class "Default")
      (node (ref "D2") (pin "2") (pinfunction "K_2") (pintype "passive"))
      (node (ref "R2") (pin "1") (pinfunction "1_1") (pintype "passive"))
    )
    (net (code "40") (name "Net-(D3-K)") (class "Default")
      (node (ref "D3") (pin "2") (pinfunction "K_2") (pintype "passive"))
      (node (ref "R3") (pin "1") (pinfunction "1_1") (pintype "passive"))
    )
    (net (code "41") (name "Net-(J1-VBUS)") (class "Default")
      (node (ref "C24") (pin "1") (pinfunction "1_1") (pintype "passive"))
      (node (ref "FB1") (pin "1") (pinfunction "1_1") (pintype "passive"))
      (node (ref "J1") (pin "1") (pinfunction "VBUS_1") (pintype "passive"))
    )
    (net (code "42") (name "Net-(U1B-BOOT0)") (class "Default")
      (node (ref "R5") (pin "1") (pinfunction "1_1") (pintype "passive"))
      (node (ref "U1") (pin "138") (pinfunction "BOOT0_138") (pintype "input"))
    )
    (net (code "43") (name "Net-(U1B-PDR_ON)") (class "Default")
      (node (ref "R4") (pin "1") (pinfunction "1_1") (pintype "passive"))
      (node (ref "U1") (pin "143") (pinfunction "PDR_ON_143") (pintype "input"))
    )
    (net (code "44") (name "Net-(U1B-PH0-OSC_IN(PH0))") (class "Default")
      (node (ref "C1") (pin "1") (pinfunction "1_1") (pintype "passive"))
      (node (ref "U1") (pin "23") (pinfunction "PH0-OSC_IN(PH0)_23") (pintype "bidirectional"))
      (node (ref "Y2") (pin "1") (pinfunction "IN_1") (pintype "passive"))
    )
    (net (code "45") (name "Net-(U1B-PH1-OSC_OUT(PH1))") (class "Default")
      (node (ref "C2") (pin "1") (pinfunction "1_1") (pintype "passive"))
      (node (ref "U1") (pin "24") (pinfunction "PH1-OSC_OUT(PH1)_24") (pintype "bidirectional"))
      (node (ref "Y2") (pin "3") (pinfunction "OUT_3") (pintype "passive"))
    )
    (net (code "46") (name "Net-(U1B-VCAP_1)") (class "Default")
      (node (ref "C7") (pin "2") (pinfunction "2_2") (pintype "passive"))
      (node (ref "U1") (pin "71") (pinfunction "VCAP_1_71") (pintype "passive"))
    )
    (net (code "47") (name "Net-(U1B-VCAP_2)") (class "Default")
      (node (ref "C6") (pin "2") (pinfunction "2_2") (pintype "passive"))
      (node (ref "U1") (pin "106") (pinfunction "VCAP_2_106") (pintype "passive"))
    )
    (net (code "48") (name "VDD") (class "Default")
      (node (ref "C10") (pin "1") (pinfunction "1_1") (pintype "passive"))
      (node (ref "C11") (pin "1") (pinfunction "1_1") (pintype "passive"))
      (node (ref "C12") (pin "2") (pinfunction "2_2") (pintype "passive"))
      (node (ref "C13") (pin "2") (pinfunction "2_2") (pintype "passive"))
      (node (ref "C14") (pin "2") (pinfunction "2_2") (pintype "passive"))
      (node (ref "C15") (pin "2") (pinfunction "2_2") (pintype "passive"))
      (node (ref "C16") (pin "2") (pinfunction "2_2") (pintype "passive"))
      (node (ref "C17") (pin "2") (pinfunction "2_2") (pintype "passive"))
      (node (ref "C18") (pin "2") (pinfunction "2_2") (pintype "passive"))
      (node (ref "C19") (pin "2") (pinfunction "2_2") (pintype "passive"))
      (node (ref "C20") (pin "2") (pinfunction "2_2") (pintype "passive"))
      (node (ref "C21") (pin "2") (pinfunction "2_2") (pintype "passive"))
      (node (ref "C22") (pin "2") (pinfunction "2_2") (pintype "passive"))
      (node (ref "C28") (pin "1") (pinfunction "1_1") (pintype "passive"))
      (node (ref "C29") (pin "2") (pinfunction "2_2") (pintype "passive"))
      (node (ref "C3") (pin "2") (pinfunction "2_2") (pintype "passive"))
      (node (ref "C30") (pin "1") (pinfunction "1_1") (pintype "passive"))
      (node (ref "C31") (pin "2") (pinfunction "2_2") (pintype "passive"))
      (node (ref "C32") (pin "1") (pinfunction "1_1") (pintype "passive"))
      (node (ref "C4") (pin "1") (pinfunction "1_1") (pintype "passive"))
      (node (ref "C8") (pin "1") (pinfunction "1_1") (pintype "passive"))
      (node (ref "C9") (pin "2") (pinfunction "2_2") (pintype "passive"))
      (node (ref "D1") (pin "1") (pinfunction "A_1") (pintype "passive"))
      (node (ref "D2") (pin "1") (pinfunction "A_1") (pintype "passive"))
      (node (ref "D3") (pin "1") (pinfunction "A_1") (pintype "passive"))
      (node (ref "J2") (pin "1") (pinfunction "1_1") (pintype "passive"))
      (node (ref "J3") (pin "1") (pinfunction "1_1") (pintype "passive"))
      (node (ref "J4") (pin "1") (pinfunction "1_1") (pintype "passive"))
      (node (ref "J4") (pin "2") (pinfunction "2_2") (pintype "passive"))
      (node (ref "R4") (pin "2") (pinfunction "2_2") (pintype "passive"))
      (node (ref "R6") (pin "2") (pinfunction "2_2") (pintype "passive"))
      (node (ref "R7") (pin "2") (pinfunction "2_2") (pintype "passive"))
      (node (ref "U1") (pin "108") (pinfunction "VDD_108") (pintype "power_in"))
      (node (ref "U1") (pin "121") (pinfunction "VDD_121") (pintype "power_in"))
      (node (ref "U1") (pin "131") (pinfunction "VDD_131") (pintype "power_in"))
      (node (ref "U1") (pin "144") (pinfunction "VDD_144") (pintype "power_in"))
      (node (ref "U1") (pin "17") (pinfunction "VDD_17") (pintype "power_in"))
      (node (ref "U1") (pin "30") (pinfunction "VDD_30") (pintype "power_in"))
      (node (ref "U1") (pin "32") (pinfunction "VREF+_32") (pintype "power_in"))
      (node (ref "U1") (pin "33") (pinfunction "VDDA_33") (pintype "power_in"))
      (node (ref "U1") (pin "39") (pinfunction "VDD_39") (pintype "power_in"))
      (node (ref "U1") (pin "52") (pinfunction "VDD_52") (pintype "power_in"))
      (node (ref "U1") (pin "6") (pinfunction "VBAT_6") (pintype "power_in"))
      (node (ref "U1") (pin "62") (pinfunction "VDD_62") (pintype "power_in"))
      (node (ref "U1") (pin "72") (pinfunction "VDD_72") (pintype "power_in"))
      (node (ref "U1") (pin "84") (pinfunction "VDD_84") (pintype "power_in"))
      (node (ref "U1") (pin "95") (pinfunction "VDDUSB_95") (pintype "power_in"))
      (node (ref "U2") (pin "3") (pinfunction "VOUT_3") (pintype "power_in"))
      (node (ref "U4") (pin "5") (pinfunction "VDD_5") (pintype "power_in"))
      (node (ref "U5") (pin "1") (pinfunction "VCC_1") (pintype "power_in"))
      (node (ref "U6") (pin "5") (pinfunction "VDD_5") (pintype "power_in"))
      (node (ref "Y1") (pin "1") (pinfunction "~{Tri-State}_1") (pintype "input"))
      (node (ref "Y1") (pin "4") (pinfunction "VDD_4") (pintype "power_in"))
    )
    (net (code "49") (name "unconnected-(J1-ID-Pad4)") (class "Default")
      (node (ref "J1") (pin "4") (pinfunction "ID_4") (pintype "passive+no_connect"))
    )
    (net (code "50") (name "unconnected-(J2-Pad4)") (class "Default")
      (node (ref "J2") (pin "4") (pinfunction "4_4") (pintype "passive+no_connect"))
    )
    (net (code "51") (name "unconnected-(J2-Pad6)") (class "Default")
      (node (ref "J2") (pin "6") (pinfunction "6_6") (pintype "passive+no_connect"))
    )
    (net (code "52") (name "unconnected-(J4-Pad3)") (class "Default")
      (node (ref "J4") (pin "3") (pinfunction "3_3") (pintype "passive"))
    )
    (net (code "53") (name "unconnected-(J4-Pad5)") (class "Default")
      (node (ref "J4") (pin "5") (pinfunction "5_5") (pintype "passive"))
    )
    (net (code "54") (name "unconnected-(J4-Pad11)") (class "Default")
      (node (ref "J4") (pin "11") (pinfunction "11_11") (pintype "passive"))
    )
    (net (code "55") (name "unconnected-(J4-Pad17)") (class "Default")
      (node (ref "J4") (pin "17") (pinfunction "17_17") (pintype "passive"))
    )
    (net (code "56") (name "unconnected-(J4-Pad19)") (class "Default")
      (node (ref "J4") (pin "19") (pinfunction "19_19") (pintype "passive+no_connect"))
    )
    (net (code "57") (name "unconnected-(SW2-Pad2)") (class "Default")
      (node (ref "SW2") (pin "2") (pinfunction "2_2") (pintype "passive+no_connect"))
    )
    (net (code "58") (name "unconnected-(SW2-Pad4)") (class "Default")
      (node (ref "SW2") (pin "4") (pinfunction "4_4") (pintype "passive+no_connect"))
    )
    (net (code "59") (name "unconnected-(U1A-PA0-WKUP(PA0)-Pad34)") (class "Default")
      (node (ref "U1") (pin "34") (pinfunction "PA0-WKUP(PA0)_34") (pintype "bidirectional+no_connect"))
    )
    (net (code "60") (name "unconnected-(U1A-PA1-Pad35)") (class "Default")
      (node (ref "U1") (pin "35") (pinfunction "PA1_35") (pintype "bidirectional+no_connect"))
    )
    (net (code "61") (name "unconnected-(U1A-PA8-Pad100)") (class "Default")
      (node (ref "U1") (pin "100") (pinfunction "PA8_100") (pintype "bidirectional+no_connect"))
    )
    (net (code "62") (name "unconnected-(U1A-PA15(JTDI)-Pad110)") (class "Default")
      (node (ref "U1") (pin "110") (pinfunction "PA15(JTDI)_110") (pintype "bidirectional+no_connect"))
    )
    (net (code "63") (name "unconnected-(U1A-PB2-BOOT1(PB2)-Pad48)") (class "Default")
      (node (ref "U1") (pin "48") (pinfunction "PB2-BOOT1(PB2)_48") (pintype "bidirectional+no_connect"))
    )
    (net (code "64") (name "unconnected-(U1A-PB4(NJTRST)-Pad134)") (class "Default")
      (node (ref "U1") (pin "134") (pinfunction "PB4(NJTRST)_134") (pintype "bidirectional+no_connect"))
    )
    (net (code "65") (name "unconnected-(U1A-PB5-Pad135)") (class "Default")
      (node (ref "U1") (pin "135") (pinfunction "PB5_135") (pintype "bidirectional+no_connect"))
    )
    (net (code "66") (name "unconnected-(U1A-PB6-Pad136)") (class "Default")
      (node (ref "U1") (pin "136") (pinfunction "PB6_136") (pintype "bidirectional+no_connect"))
    )
    (net (code "67") (name "unconnected-(U1A-PB7-Pad137)") (class "Default")
      (node (ref "U1") (pin "137") (pinfunction "PB7_137") (pintype "bidirectional+no_connect"))
    )
    (net (code "68") (name "unconnected-(U1A-PB8-Pad139)") (class "Default")
      (node (ref "U1") (pin "139") (pinfunction "PB8_139") (pintype "bidirectional+no_connect"))
    )
    (net (code "69") (name "unconnected-(U1A-PB9-Pad140)") (class "Default")
      (node (ref "U1") (pin "140") (pinfunction "PB9_140") (pintype "bidirectional+no_connect"))
    )
    (net (code "70") (name "unconnected-(U1A-PB11-Pad70)") (class "Default")
      (node (ref "U1") (pin "70") (pinfunction "PB11_70") (pintype "bidirectional+no_connect"))
    )
    (net (code "71") (name "unconnected-(U1A-PB12-Pad73)") (class "Default")
      (node (ref "U1") (pin "73") (pinfunction "PB12_73") (pintype "bidirectional+no_connect"))
    )
    (net (code "72") (name "unconnected-(U1A-PB13-Pad74)") (class "Default")
      (node (ref "U1") (pin "74") (pinfunction "PB13_74") (pintype "bidirectional+no_connect"))
    )
    (net (code "73") (name "unconnected-(U1A-PB14-Pad75)") (class "Default")
      (node (ref "U1") (pin "75") (pinfunction "PB14_75") (pintype "bidirectional+no_connect"))
    )
    (net (code "74") (name "unconnected-(U1A-PB15-Pad76)") (class "Default")
      (node (ref "U1") (pin "76") (pinfunction "PB15_76") (pintype "bidirectional+no_connect"))
    )
    (net (code "75") (name "unconnected-(U1A-PC0-Pad26)") (class "Default")
      (node (ref "U1") (pin "26") (pinfunction "PC0_26") (pintype "bidirectional+no_connect"))
    )
    (net (code "76") (name "unconnected-(U1A-PC1-Pad27)") (class "Default")
      (node (ref "U1") (pin "27") (pinfunction "PC1_27") (pintype "bidirectional+no_connect"))
    )
    (net (code "77") (name "unconnected-(U1A-PC2-Pad28)") (class "Default")
      (node (ref "U1") (pin "28") (pinfunction "PC2_28") (pintype "bidirectional+no_connect"))
    )
    (net (code "78") (name "unconnected-(U1A-PC3-Pad29)") (class "Default")
      (node (ref "U1") (pin "29") (pinfunction "PC3_29") (pintype "bidirectional+no_connect"))
    )
    (net (code "79") (name "unconnected-(U1A-PC4-Pad44)") (class "Default")
      (node (ref "U1") (pin "44") (pinfunction "PC4_44") (pintype "bidirectional+no_connect"))
    )
    (net (code "80") (name "unconnected-(U1A-PC6-Pad96)") (class "Default")
      (node (ref "U1") (pin "96") (pinfunction "PC6_96") (pintype "bidirectional+no_connect"))
    )
    (net (code "81") (name "unconnected-(U1A-PC7-Pad97)") (class "Default")
      (node (ref "U1") (pin "97") (pinfunction "PC7_97") (pintype "bidirectional+no_connect"))
    )
    (net (code "82") (name "unconnected-(U1A-PC8-Pad98)") (class "Default")
      (node (ref "U1") (pin "98") (pinfunction "PC8_98") (pintype "bidirectional+no_connect"))
    )
    (net (code "83") (name "unconnected-(U1A-PC10-Pad111)") (class "Default")
      (node (ref "U1") (pin "111") (pinfunction "PC10_111") (pintype "bidirectional+no_connect"))
    )
    (net (code "84") (name "unconnected-(U1A-PC11-Pad112)") (class "Default")
      (node (ref "U1") (pin "112") (pinfunction "PC11_112") (pintype "bidirectional+no_connect"))
    )
    (net (code "85") (name "unconnected-(U1A-PC12-Pad113)") (class "Default")
      (node (ref "U1") (pin "113") (pinfunction "PC12_113") (pintype "bidirectional+no_connect"))
    )
    (net (code "86") (name "unconnected-(U1A-PC14-OSC32_IN(PC14)-Pad8)") (class "Default")
      (node (ref "U1") (pin "8") (pinfunction "PC14-OSC32_IN(PC14)_8") (pintype "bidirectional+no_connect"))
    )
    (net (code "87") (name "unconnected-(U1A-PC15-OSC32_OUT(PC15)-Pad9)") (class "Default")
      (node (ref "U1") (pin "9") (pinfunction "PC15-OSC32_OUT(PC15)_9") (pintype "bidirectional+no_connect"))
    )
    (net (code "88") (name "unconnected-(U1A-PD0-Pad114)") (class "Default")
      (node (ref "U1") (pin "114") (pinfunction "PD0_114") (pintype "bidirectional+no_connect"))
    )
    (net (code "89") (name "unconnected-(U1A-PD1-Pad115)") (class "Default")
      (node (ref "U1") (pin "115") (pinfunction "PD1_115") (pintype "bidirectional+no_connect"))
    )
    (net (code "90") (name "unconnected-(U1A-PD2-Pad116)") (class "Default")
      (node (ref "U1") (pin "116") (pinfunction "PD2_116") (pintype "bidirectional+no_connect"))
    )
    (net (code "91") (name "unconnected-(U1A-PD3-Pad117)") (class "Default")
      (node (ref "U1") (pin "117") (pinfunction "PD3_117") (pintype "bidirectional+no_connect"))
    )
    (net (code "92") (name "unconnected-(U1A-PD4-Pad118)") (class "Default")
      (node (ref "U1") (pin "118") (pinfunction "PD4_118") (pintype "bidirectional+no_connect"))
    )
    (net (code "93") (name "unconnected-(U1A-PD6-Pad122)") (class "Default")
      (node (ref "U1") (pin "122") (pinfunction "PD6_122") (pintype "bidirectional+no_connect"))
    )
    (net (code "94") (name "unconnected-(U1A-PD7-Pad123)") (class "Default")
      (node (ref "U1") (pin "123") (pinfunction "PD7_123") (pintype "bidirectional+no_connect"))
    )
    (net (code "95") (name "unconnected-(U1A-PD10-Pad79)") (class "Default")
      (node (ref "U1") (pin "79") (pinfunction "PD10_79") (pintype "bidirectional+no_connect"))
    )
    (net (code "96") (name "unconnected-(U1A-PD11-Pad80)") (class "Default")
      (node (ref "U1") (pin "80") (pinfunction "PD11_80") (pintype "bidirectional+no_connect"))
    )
    (net (code "97") (name "unconnected-(U1A-PD12-Pad81)") (class "Default")
      (node (ref "U1") (pin "81") (pinfunction "PD12_81") (pintype "bidirectional+no_connect"))
    )
    (net (code "98") (name "unconnected-(U1A-PD13-Pad82)") (class "Default")
      (node (ref "U1") (pin "82") (pinfunction "PD13_82") (pintype "bidirectional+no_connect"))
    )
    (net (code "99") (name "unconnected-(U1A-PD14-Pad85)") (class "Default")
      (node (ref "U1") (pin "85") (pinfunction "PD14_85") (pintype "bidirectional+no_connect"))
    )
    (net (code "100") (name "unconnected-(U1A-PD15-Pad86)") (class "Default")
      (node (ref "U1") (pin "86") (pinfunction "PD15_86") (pintype "bidirectional+no_connect"))
    )
    (net (code "101") (name "unconnected-(U1A-PE0-Pad141)") (class "Default")
      (node (ref "U1") (pin "141") (pinfunction "PE0_141") (pintype "bidirectional+no_connect"))
    )
    (net (code "102") (name "unconnected-(U1A-PE1-Pad142)") (class "Default")
      (node (ref "U1") (pin "142") (pinfunction "PE1_142") (pintype "bidirectional+no_connect"))
    )
    (net (code "103") (name "unconnected-(U1A-PE2-Pad1)") (class "Default")
      (node (ref "U1") (pin "1") (pinfunction "PE2_1") (pintype "bidirectional+no_connect"))
    )
    (net (code "104") (name "unconnected-(U1A-PE4-Pad3)") (class "Default")
      (node (ref "U1") (pin "3") (pinfunction "PE4_3") (pintype "bidirectional+no_connect"))
    )
    (net (code "105") (name "unconnected-(U1A-PE5-Pad4)") (class "Default")
      (node (ref "U1") (pin "4") (pinfunction "PE5_4") (pintype "bidirectional+no_connect"))
    )
    (net (code "106") (name "unconnected-(U1A-PE6-Pad5)") (class "Default")
      (node (ref "U1") (pin "5") (pinfunction "PE6_5") (pintype "bidirectional+no_connect"))
    )
    (net (code "107") (name "unconnected-(U1A-PE7-Pad58)") (class "Default")
      (node (ref "U1") (pin "58") (pinfunction "PE7_58") (pintype "bidirectional+no_connect"))
    )
    (net (code "108") (name "unconnected-(U1A-PE8-Pad59)") (class "Default")
      (node (ref "U1") (pin "59") (pinfunction "PE8_59") (pintype "bidirectional+no_connect"))
    )
    (net (code "109") (name "unconnected-(U1A-PE10-Pad63)") (class "Default")
      (node (ref "U1") (pin "63") (pinfunction "PE10_63") (pintype "bidirectional+no_connect"))
    )
    (net (code "110") (name "unconnected-(U1A-PE11-Pad64)") (class "Default")
      (node (ref "U1") (pin "64") (pinfunction "PE11_64") (pintype "bidirectional+no_connect"))
    )
    (net (code "111") (name "unconnected-(U1A-PE12-Pad65)") (class "Default")
      (node (ref "U1") (pin "65") (pinfunction "PE12_65") (pintype "bidirectional+no_connect"))
    )
    (net (code "112") (name "unconnected-(U1A-PE13-Pad66)") (class "Default")
      (node (ref "U1") (pin "66") (pinfunction "PE13_66") (pintype "bidirectional+no_connect"))
    )
    (net (code "113") (name "unconnected-(U1A-PE14-Pad67)") (class "Default")
      (node (ref "U1") (pin "67") (pinfunction "PE14_67") (pintype "bidirectional+no_connect"))
    )
    (net (code "114") (name "unconnected-(U1A-PE15-Pad68)") (class "Default")
      (node (ref "U1") (pin "68") (pinfunction "PE15_68") (pintype "bidirectional+no_connect"))
    )
    (net (code "115") (name "unconnected-(U1A-PF0-Pad10)") (class "Default")
      (node (ref "U1") (pin "10") (pinfunction "PF0_10") (pintype "bidirectional+no_connect"))
    )
    (net (code "116") (name "unconnected-(U1A-PF1-Pad11)") (class "Default")
      (node (ref "U1") (pin "11") (pinfunction "PF1_11") (pintype "bidirectional+no_connect"))
    )
    (net (code "117") (name "unconnected-(U1A-PF2-Pad12)") (class "Default")
      (node (ref "U1") (pin "12") (pinfunction "PF2_12") (pintype "bidirectional+no_connect"))
    )
    (net (code "118") (name "unconnected-(U1A-PF6-Pad18)") (class "Default")
      (node (ref "U1") (pin "18") (pinfunction "PF6_18") (pintype "bidirectional+no_connect"))
    )
    (net (code "119") (name "unconnected-(U1A-PF7-Pad19)") (class "Default")
      (node (ref "U1") (pin "19") (pinfunction "PF7_19") (pintype "bidirectional+no_connect"))
    )
    (net (code "120") (name "unconnected-(U1A-PF10-Pad22)") (class "Default")
      (node (ref "U1") (pin "22") (pinfunction "PF10_22") (pintype "bidirectional+no_connect"))
    )
    (net (code "121") (name "unconnected-(U1A-PF11-Pad49)") (class "Default")
      (node (ref "U1") (pin "49") (pinfunction "PF11_49") (pintype "bidirectional+no_connect"))
    )
    (net (code "122") (name "unconnected-(U1A-PF12-Pad50)") (class "Default")
      (node (ref "U1") (pin "50") (pinfunction "PF12_50") (pintype "bidirectional+no_connect"))
    )
    (net (code "123") (name "unconnected-(U1A-PF13-Pad53)") (class "Default")
      (node (ref "U1") (pin "53") (pinfunction "PF13_53") (pintype "bidirectional+no_connect"))
    )
    (net (code "124") (name "unconnected-(U1A-PF14-Pad54)") (class "Default")
      (node (ref "U1") (pin "54") (pinfunction "PF14_54") (pintype "bidirectional+no_connect"))
    )
    (net (code "125") (name "unconnected-(U1A-PF15-Pad55)") (class "Default")
      (node (ref "U1") (pin "55") (pinfunction "PF15_55") (pintype "bidirectional+no_connect"))
    )
    (net (code "126") (name "unconnected-(U1B-PG0-Pad56)") (class "Default")
      (node (ref "U1") (pin "56") (pinfunction "PG0_56") (pintype "bidirectional+no_connect"))
    )
    (net (code "127") (name "unconnected-(U1B-PG1-Pad57)") (class "Default")
      (node (ref "U1") (pin "57") (pinfunction "PG1_57") (pintype "bidirectional+no_connect"))
    )
    (net (code "128") (name "unconnected-(U1B-PG2-Pad87)") (class "Default")
      (node (ref "U1") (pin "87") (pinfunction "PG2_87") (pintype "bidirectional+no_connect"))
    )
    (net (code "129") (name "unconnected-(U1B-PG3-Pad88)") (class "Default")
      (node (ref "U1") (pin "88") (pinfunction "PG3_88") (pintype "bidirectional+no_connect"))
    )
    (net (code "130") (name "unconnected-(U1B-PG4-Pad89)") (class "Default")
      (node (ref "U1") (pin "89") (pinfunction "PG4_89") (pintype "bidirectional+no_connect"))
    )
    (net (code "131") (name "unconnected-(U1B-PG6-Pad91)") (class "Default")
      (node (ref "U1") (pin "91") (pinfunction "PG6_91") (pintype "bidirectional+no_connect"))
    )
    (net (code "132") (name "unconnected-(U1B-PG7-Pad92)") (class "Default")
      (node (ref "U1") (pin "92") (pinfunction "PG7_92") (pintype "bidirectional+no_connect"))
    )
    (net (code "133") (name "unconnected-(U1B-PG8-Pad93)") (class "Default")
      (node (ref "U1") (pin "93") (pinfunction "PG8_93") (pintype "bidirectional+no_connect"))
    )
    (net (code "134") (name "unconnected-(U1B-PG9-Pad124)") (class "Default")
      (node (ref "U1") (pin "124") (pinfunction "PG9_124") (pintype "bidirectional+no_connect"))
    )
    (net (code "135") (name "unconnected-(U1B-PG10-Pad125)") (class "Default")
      (node (ref "U1") (pin "125") (pinfunction "PG10_125") (pintype "bidirectional+no_connect"))
    )
    (net (code "136") (name "unconnected-(U1B-PG11-Pad126)") (class "Default")
      (node (ref "U1") (pin "126") (pinfunction "PG11_126") (pintype "bidirectional+no_connect"))
    )
    (net (code "137") (name "unconnected-(U1B-PG12-Pad127)") (class "Default")
      (node (ref "U1") (pin "127") (pinfunction "PG12_127") (pintype "bidirectional+no_connect"))
    )
    (net (code "138") (name "unconnected-(U1B-PG13-Pad128)") (class "Default")
      (node (ref "U1") (pin "128") (pinfunction "PG13_128") (pintype "bidirectional+no_connect"))
    )
    (net (code "139") (name "unconnected-(U1B-PG14-Pad129)") (class "Default")
      (node (ref "U1") (pin "129") (pinfunction "PG14_129") (pintype "bidirectional+no_connect"))
    )
    (net (code "140") (name "unconnected-(U1B-PG15-Pad132)") (class "Default")
      (node (ref "U1") (pin "132") (pinfunction "PG15_132") (pintype "bidirectional+no_connect"))
    )
    (net (code "141") (name "unconnected-(U7-G3-Pad12)") (class "Default")
      (node (ref "U7") (pin "12") (pinfunction "G3_12") (pintype "passive+no_connect"))
    )
    (net (code "142") (name "unconnected-(U7-G4-Pad13)") (class "Default")
      (node (ref "U7") (pin "13") (pinfunction "G4_13") (pintype "passive+no_connect"))
    )
    (net (code "143") (name "unconnected-(U7-G5-Pad14)") (class "Default")
      (node (ref "U7") (pin "14") (pinfunction "G5_14") (pintype "passive+no_connect"))
    )
  )
)
